# 04_16_2016_02.net
KiCad netlist of a schematic drawn in EAGLE
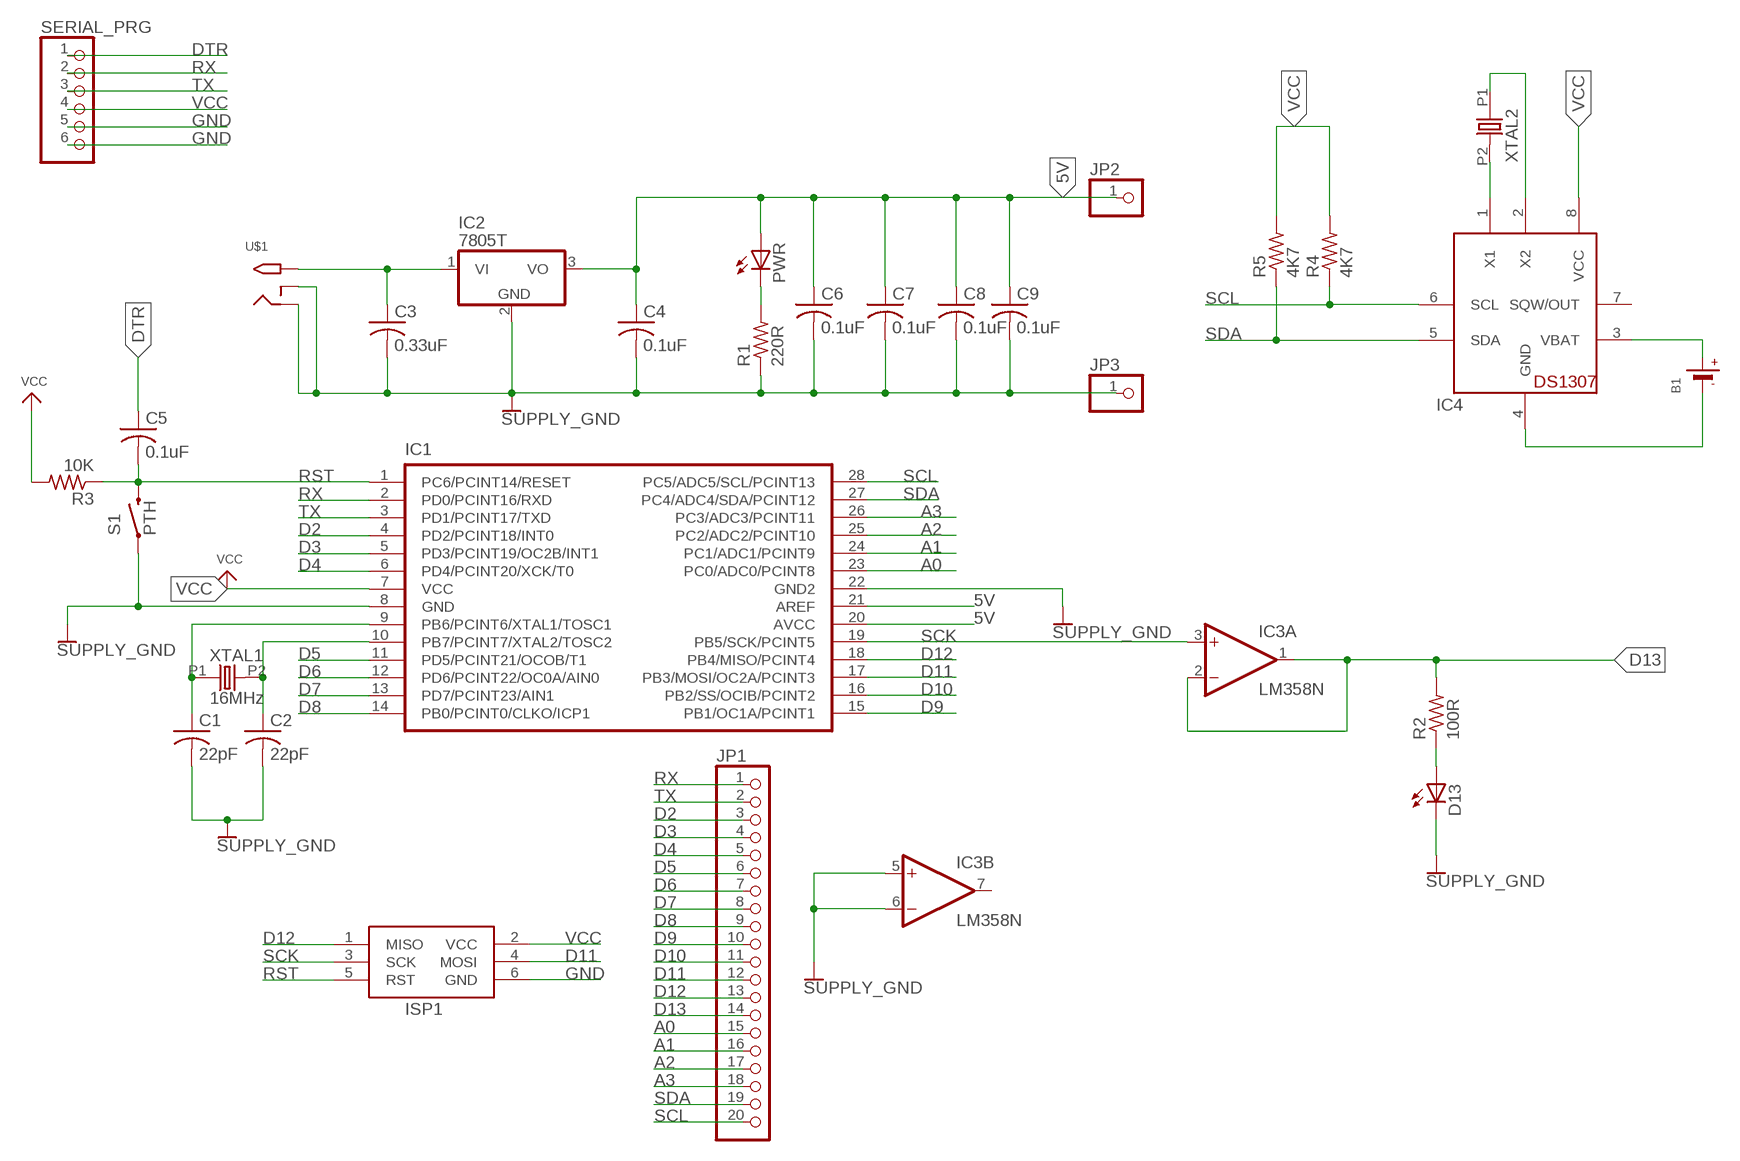
[diagram p0: schematic, sheet 1]

(export (version "E")
  (design (tool "Eeschema 10.0.6"))
  (components
    (comp (ref "B1")
      (value "BATTERYCR2032")
      (footprint "eagle-import:CR2032")
      (libsource (lib "eagle-import") (part "BATTERYCR2032"))
    )
    (comp (ref "C1")
      (value "22pF")
      (footprint "eagle-import:C050-025X075")
      (libsource (lib "eagle-import") (part "C-US050-025X075"))
    )
    (comp (ref "C2")
      (value "22pF")
      (footprint "eagle-import:C050-025X075")
      (libsource (lib "eagle-import") (part "C-US050-025X075"))
    )
    (comp (ref "C3")
      (value "0.33uF")
      (footprint "eagle-import:C050-025X075")
      (libsource (lib "eagle-import") (part "C-US050-025X075"))
    )
    (comp (ref "C4")
      (value "0.1uF")
      (footprint "eagle-import:C050-025X075")
      (libsource (lib "eagle-import") (part "C-US050-025X075"))
    )
    (comp (ref "C5")
      (value "0.1uF")
      (footprint "eagle-import:C050-025X075")
      (libsource (lib "eagle-import") (part "C-US050-025X075"))
    )
    (comp (ref "C6")
      (value "0.1uF")
      (footprint "eagle-import:C050-025X075")
      (libsource (lib "eagle-import") (part "C-US050-025X075"))
    )
    (comp (ref "C7")
      (value "0.1uF")
      (footprint "eagle-import:C050-025X075")
      (libsource (lib "eagle-import") (part "C-US050-025X075"))
    )
    (comp (ref "C8")
      (value "0.1uF")
      (footprint "eagle-import:C050-025X075")
      (libsource (lib "eagle-import") (part "C-US050-025X075"))
    )
    (comp (ref "C9")
      (value "0.1uF")
      (footprint "eagle-import:C050-025X075")
      (libsource (lib "eagle-import") (part "C-US050-025X075"))
    )
    (comp (ref "D13")
      (value "LED5MM")
      (footprint "eagle-import:LED5MM")
      (libsource (lib "eagle-import") (part "LED5MM"))
    )
    (comp (ref "IC1")
      (value "IC_UC_ATMEGA328PDIL")
      (footprint "eagle-import:DIL28-N")
      (libsource (lib "eagle-import") (part "IC_UC_ATMEGA328PDIL"))
    )
    (comp (ref "IC2")
      (value "7805T")
      (footprint "eagle-import:TO220H")
      (libsource (lib "eagle-import") (part "78T05"))
    )
    (comp (ref "IC3")
      (value "LM358N")
      (footprint "eagle-import:DIL08")
      (libsource (lib "eagle-import") (part "LM358N"))
    )
    (comp (ref "IC4")
      (value "DS1307")
      (footprint "eagle-import:DIL08")
      (libsource (lib "eagle-import") (part "DS1307"))
    )
    (comp (ref "ISP1")
      (value "AVRISP-6")
      (footprint "eagle-import:AVRISP")
      (libsource (lib "eagle-import") (part "AVRISP-6"))
    )
    (comp (ref "JP1")
      (value "PINHD-1X20-BIG")
      (footprint "eagle-import:1X20-BIG")
      (libsource (lib "eagle-import") (part "PINHD-1X20-BIG"))
    )
    (comp (ref "JP2")
      (value "PINHD-1X1")
      (footprint "eagle-import:1X01")
      (libsource (lib "eagle-import") (part "PINHD-1X1"))
    )
    (comp (ref "JP3")
      (value "PINHD-1X1")
      (footprint "eagle-import:1X01")
      (libsource (lib "eagle-import") (part "PINHD-1X1"))
    )
    (comp (ref "PWR")
      (value "LED5MM")
      (footprint "eagle-import:LED5MM")
      (libsource (lib "eagle-import") (part "LED5MM"))
    )
    (comp (ref "R1")
      (value "220R")
      (footprint "eagle-import:0207_10")
      (libsource (lib "eagle-import") (part "R-US_0207/10"))
    )
    (comp (ref "R2")
      (value "100R")
      (footprint "eagle-import:0207_10")
      (libsource (lib "eagle-import") (part "R-US_0207/10"))
    )
    (comp (ref "R3")
      (value "10K")
      (footprint "eagle-import:0207_10")
      (libsource (lib "eagle-import") (part "R-US_0207/10"))
    )
    (comp (ref "R4")
      (value "4K7")
      (footprint "eagle-import:0207_10")
      (libsource (lib "eagle-import") (part "R-US_0207/10"))
    )
    (comp (ref "R5")
      (value "4K7")
      (footprint "eagle-import:0207_10")
      (libsource (lib "eagle-import") (part "R-US_0207/10"))
    )
    (comp (ref "S1")
      (value "PTH")
      (footprint "eagle-import:TACTILE-PTH")
      (libsource (lib "eagle-import") (part "SWITCH-MOMENTARY-2PTH"))
    )
    (comp (ref "SERIAL_PRG")
      (value "PINHD-1X6")
      (footprint "eagle-import:1X06")
      (libsource (lib "eagle-import") (part "PINHD-1X6"))
    )
    (comp (ref "U$1")
      (value "2.1MMJACKTHM")
      (footprint "eagle-import:PJ-102A")
      (libsource (lib "eagle-import") (part "2.1MMJACKTHM"))
    )
    (comp (ref "XTAL1")
      (value "16MHz")
      (footprint "eagle-import:HC-49U-PTH")
      (libsource (lib "eagle-import") (part "OSC-XTAL-HC-49U-PTH"))
    )
    (comp (ref "XTAL2")
      (value "OSC-XTALTC-26")
      (footprint "eagle-import:TC-26")
      (libsource (lib "eagle-import") (part "OSC-XTALTC-26"))
    )
  )
  (nets
    (net (code "1") (name "/A0") (class "Default")
      (node (ref "IC1") (pin "23") (pinfunction "PC0/ADC0/PCINT8_23") (pintype "bidirectional"))
      (node (ref "JP1") (pin "15") (pinfunction "15_15") (pintype "passive"))
    )
    (net (code "2") (name "/A1") (class "Default")
      (node (ref "IC1") (pin "24") (pinfunction "PC1/ADC1/PCINT9_24") (pintype "bidirectional"))
      (node (ref "JP1") (pin "16") (pinfunction "16_16") (pintype "passive"))
    )
    (net (code "3") (name "/A2") (class "Default")
      (node (ref "IC1") (pin "25") (pinfunction "PC2/ADC2/PCINT10_25") (pintype "bidirectional"))
      (node (ref "JP1") (pin "17") (pinfunction "17_17") (pintype "passive"))
    )
    (net (code "4") (name "/A3") (class "Default")
      (node (ref "IC1") (pin "26") (pinfunction "PC3/ADC3/PCINT11_26") (pintype "bidirectional"))
      (node (ref "JP1") (pin "18") (pinfunction "18_18") (pintype "passive"))
    )
    (net (code "5") (name "/D2") (class "Default")
      (node (ref "IC1") (pin "4") (pinfunction "PD2/PCINT18/INT0_4") (pintype "bidirectional"))
      (node (ref "JP1") (pin "3") (pinfunction "3_3") (pintype "passive"))
    )
    (net (code "6") (name "/D3") (class "Default")
      (node (ref "IC1") (pin "5") (pinfunction "PD3/PCINT19/OC2B/INT1_5") (pintype "bidirectional"))
      (node (ref "JP1") (pin "4") (pinfunction "4_4") (pintype "passive"))
    )
    (net (code "7") (name "/D4") (class "Default")
      (node (ref "IC1") (pin "6") (pinfunction "PD4/PCINT20/XCK/T0_6") (pintype "bidirectional"))
      (node (ref "JP1") (pin "5") (pinfunction "5_5") (pintype "passive"))
    )
    (net (code "8") (name "/D5") (class "Default")
      (node (ref "IC1") (pin "11") (pinfunction "PD5/PCINT21/OCOB/T1_11") (pintype "bidirectional"))
      (node (ref "JP1") (pin "6") (pinfunction "6_6") (pintype "passive"))
    )
    (net (code "9") (name "/D6") (class "Default")
      (node (ref "IC1") (pin "12") (pinfunction "PD6/PCINT22/OC0A/AIN0_12") (pintype "bidirectional"))
      (node (ref "JP1") (pin "7") (pinfunction "7_7") (pintype "passive"))
    )
    (net (code "10") (name "/D7") (class "Default")
      (node (ref "IC1") (pin "13") (pinfunction "PD7/PCINT23/AIN1_13") (pintype "bidirectional"))
      (node (ref "JP1") (pin "8") (pinfunction "8_8") (pintype "passive"))
    )
    (net (code "11") (name "/D8") (class "Default")
      (node (ref "IC1") (pin "14") (pinfunction "PB0/PCINT0/CLKO/ICP1_14") (pintype "bidirectional"))
      (node (ref "JP1") (pin "9") (pinfunction "9_9") (pintype "passive"))
    )
    (net (code "12") (name "/D9") (class "Default")
      (node (ref "IC1") (pin "15") (pinfunction "PB1/OC1A/PCINT1_15") (pintype "bidirectional"))
      (node (ref "JP1") (pin "10") (pinfunction "10_10") (pintype "passive"))
    )
    (net (code "13") (name "/D10") (class "Default")
      (node (ref "IC1") (pin "16") (pinfunction "PB2/SS/OCIB/PCINT2_16") (pintype "bidirectional"))
      (node (ref "JP1") (pin "11") (pinfunction "11_11") (pintype "passive"))
    )
    (net (code "14") (name "/D11") (class "Default")
      (node (ref "IC1") (pin "17") (pinfunction "PB3/MOSI/OC2A/PCINT3_17") (pintype "bidirectional"))
      (node (ref "ISP1") (pin "4") (pinfunction "MOSI_4") (pintype "output"))
      (node (ref "JP1") (pin "12") (pinfunction "12_12") (pintype "passive"))
    )
    (net (code "15") (name "/D12") (class "Default")
      (node (ref "IC1") (pin "18") (pinfunction "PB4/MISO/PCINT4_18") (pintype "bidirectional"))
      (node (ref "ISP1") (pin "1") (pinfunction "MISO_1") (pintype "input"))
      (node (ref "JP1") (pin "13") (pinfunction "13_13") (pintype "passive"))
    )
    (net (code "16") (name "/RST") (class "Default")
      (node (ref "C5") (pin "2") (pinfunction "2_2") (pintype "passive"))
      (node (ref "IC1") (pin "1") (pinfunction "PC6/PCINT14/RESET_1") (pintype "bidirectional"))
      (node (ref "ISP1") (pin "5") (pinfunction "RST_5") (pintype "output"))
      (node (ref "R3") (pin "1") (pinfunction "1_1") (pintype "passive"))
      (node (ref "S1") (pin "3") (pinfunction "2_3") (pintype "passive"))
    )
    (net (code "17") (name "/RX") (class "Default")
      (node (ref "IC1") (pin "2") (pinfunction "PD0/PCINT16/RXD_2") (pintype "bidirectional"))
      (node (ref "JP1") (pin "1") (pinfunction "1_1") (pintype "passive"))
      (node (ref "SERIAL_PRG") (pin "2") (pinfunction "2_2") (pintype "passive"))
    )
    (net (code "18") (name "/SCK") (class "Default")
      (node (ref "IC1") (pin "19") (pinfunction "PB5/SCK/PCINT5_19") (pintype "bidirectional"))
      (node (ref "IC3") (pin "3") (pinfunction "+IN_3") (pintype "input"))
      (node (ref "ISP1") (pin "3") (pinfunction "SCK_3") (pintype "output"))
    )
    (net (code "19") (name "/SCL") (class "Default")
      (node (ref "IC1") (pin "28") (pinfunction "PC5/ADC5/SCL/PCINT13_28") (pintype "bidirectional"))
      (node (ref "IC4") (pin "6") (pinfunction "SCL_6") (pintype "bidirectional"))
      (node (ref "JP1") (pin "20") (pinfunction "20_20") (pintype "passive"))
      (node (ref "R4") (pin "1") (pinfunction "1_1") (pintype "passive"))
    )
    (net (code "20") (name "/SDA") (class "Default")
      (node (ref "IC1") (pin "27") (pinfunction "PC4/ADC4/SDA/PCINT12_27") (pintype "bidirectional"))
      (node (ref "IC4") (pin "5") (pinfunction "SDA_5") (pintype "bidirectional"))
      (node (ref "JP1") (pin "19") (pinfunction "19_19") (pintype "passive"))
      (node (ref "R5") (pin "1") (pinfunction "1_1") (pintype "passive"))
    )
    (net (code "21") (name "/TX") (class "Default")
      (node (ref "IC1") (pin "3") (pinfunction "PD1/PCINT17/TXD_3") (pintype "bidirectional"))
      (node (ref "JP1") (pin "2") (pinfunction "2_2") (pintype "passive"))
      (node (ref "SERIAL_PRG") (pin "3") (pinfunction "3_3") (pintype "passive"))
    )
    (net (code "22") (name "5V") (class "Default")
      (node (ref "C4") (pin "1") (pinfunction "1_1") (pintype "passive"))
      (node (ref "C6") (pin "1") (pinfunction "1_1") (pintype "passive"))
      (node (ref "C7") (pin "1") (pinfunction "1_1") (pintype "passive"))
      (node (ref "C8") (pin "1") (pinfunction "1_1") (pintype "passive"))
      (node (ref "C9") (pin "1") (pinfunction "1_1") (pintype "passive"))
      (node (ref "IC1") (pin "20") (pinfunction "AVCC_20") (pintype "bidirectional"))
      (node (ref "IC1") (pin "21") (pinfunction "AREF_21") (pintype "bidirectional"))
      (node (ref "IC2") (pin "3") (pinfunction "VO_3") (pintype "passive"))
      (node (ref "JP2") (pin "1") (pinfunction "1_1") (pintype "passive"))
      (node (ref "PWR") (pin "A") (pinfunction "A_A") (pintype "passive"))
    )
    (net (code "23") (name "D13") (class "Default")
      (node (ref "IC3") (pin "1") (pinfunction "OUT_1") (pintype "output"))
      (node (ref "IC3") (pin "2") (pinfunction "-IN_2") (pintype "input"))
      (node (ref "JP1") (pin "14") (pinfunction "14_14") (pintype "passive"))
      (node (ref "R2") (pin "2") (pinfunction "2_2") (pintype "passive"))
    )
    (net (code "24") (name "DTR") (class "Default")
      (node (ref "C5") (pin "1") (pinfunction "1_1") (pintype "passive"))
      (node (ref "SERIAL_PRG") (pin "1") (pinfunction "1_1") (pintype "passive"))
    )
    (net (code "25") (name "Net-(D13-PadA)") (class "Default")
      (node (ref "D13") (pin "A") (pinfunction "A_A") (pintype "passive"))
      (node (ref "R2") (pin "1") (pinfunction "1_1") (pintype "passive"))
    )
    (net (code "26") (name "Net-(IC1-PB6{slash}PCINT6{slash}XTAL1{slash}TOSC1)") (class "Default")
      (node (ref "C1") (pin "1") (pinfunction "1_1") (pintype "passive"))
      (node (ref "IC1") (pin "9") (pinfunction "PB6/PCINT6/XTAL1/TOSC1_9") (pintype "bidirectional"))
      (node (ref "XTAL1") (pin "P1") (pinfunction "1_P1") (pintype "passive"))
    )
    (net (code "27") (name "Net-(IC1-PB7{slash}PCINT7{slash}XTAL2{slash}TOSC2)") (class "Default")
      (node (ref "C2") (pin "1") (pinfunction "1_1") (pintype "passive"))
      (node (ref "IC1") (pin "10") (pinfunction "PB7/PCINT7/XTAL2/TOSC2_10") (pintype "bidirectional"))
      (node (ref "XTAL1") (pin "P2") (pinfunction "2_P2") (pintype "passive"))
    )
    (net (code "28") (name "Net-(IC2-VI)") (class "Default")
      (node (ref "C3") (pin "1") (pinfunction "1_1") (pintype "passive"))
      (node (ref "IC2") (pin "1") (pinfunction "VI_1") (pintype "input"))
      (node (ref "U$1") (pin "TIP") (pinfunction "TIP_TIP") (pintype "bidirectional"))
    )
    (net (code "29") (name "Net-(IC4-GND)") (class "Default")
      (node (ref "B1") (pin "-") (pinfunction "-_-") (pintype "passive"))
      (node (ref "IC4") (pin "4") (pinfunction "GND_4") (pintype "power_in"))
    )
    (net (code "30") (name "Net-(IC4-VBAT)") (class "Default")
      (node (ref "B1") (pin "+") (pinfunction "+_+") (pintype "passive"))
      (node (ref "IC4") (pin "3") (pinfunction "VBAT_3") (pintype "power_in"))
    )
    (net (code "31") (name "Net-(IC4-X1)") (class "Default")
      (node (ref "IC4") (pin "1") (pinfunction "X1_1") (pintype "passive"))
      (node (ref "XTAL2") (pin "P2") (pinfunction "2_P2") (pintype "passive"))
    )
    (net (code "32") (name "Net-(IC4-X2)") (class "Default")
      (node (ref "IC4") (pin "2") (pinfunction "X2_2") (pintype "passive"))
      (node (ref "XTAL2") (pin "P1") (pinfunction "1_P1") (pintype "passive"))
    )
    (net (code "33") (name "Net-(PWR-C)") (class "Default")
      (node (ref "PWR") (pin "K") (pinfunction "C_K") (pintype "passive"))
      (node (ref "R1") (pin "2") (pinfunction "2_2") (pintype "passive"))
    )
    (net (code "34") (name "SUPPLY_GND") (class "Default")
      (node (ref "C1") (pin "2") (pinfunction "2_2") (pintype "passive"))
      (node (ref "C2") (pin "2") (pinfunction "2_2") (pintype "passive"))
      (node (ref "C3") (pin "2") (pinfunction "2_2") (pintype "passive"))
      (node (ref "C4") (pin "2") (pinfunction "2_2") (pintype "passive"))
      (node (ref "C6") (pin "2") (pinfunction "2_2") (pintype "passive"))
      (node (ref "C7") (pin "2") (pinfunction "2_2") (pintype "passive"))
      (node (ref "C8") (pin "2") (pinfunction "2_2") (pintype "passive"))
      (node (ref "C9") (pin "2") (pinfunction "2_2") (pintype "passive"))
      (node (ref "D13") (pin "K") (pinfunction "C_K") (pintype "passive"))
      (node (ref "IC1") (pin "22") (pinfunction "GND2_22") (pintype "bidirectional"))
      (node (ref "IC1") (pin "8") (pinfunction "GND_8") (pintype "bidirectional"))
      (node (ref "IC2") (pin "2") (pinfunction "GND_2") (pintype "passive"))
      (node (ref "IC3") (pin "5") (pinfunction "+IN_5") (pintype "input"))
      (node (ref "IC3") (pin "6") (pinfunction "-IN_6") (pintype "input"))
      (node (ref "ISP1") (pin "6") (pinfunction "GND_6") (pintype "power_in"))
      (node (ref "JP3") (pin "1") (pinfunction "1_1") (pintype "passive"))
      (node (ref "R1") (pin "1") (pinfunction "1_1") (pintype "passive"))
      (node (ref "S1") (pin "1") (pinfunction "1_1") (pintype "passive"))
      (node (ref "SERIAL_PRG") (pin "5") (pinfunction "5_5") (pintype "passive"))
      (node (ref "SERIAL_PRG") (pin "6") (pinfunction "6_6") (pintype "passive"))
      (node (ref "U$1") (pin "RING") (pinfunction "RING_RING") (pintype "bidirectional"))
      (node (ref "U$1") (pin "RING_SW") (pinfunction "RING_SW_RING_SW") (pintype "bidirectional"))
    )
    (net (code "35") (name "VCC") (class "Default")
      (node (ref "IC1") (pin "7") (pinfunction "VCC_7") (pintype "bidirectional"))
      (node (ref "IC4") (pin "8") (pinfunction "VCC_8") (pintype "power_in"))
      (node (ref "ISP1") (pin "2") (pinfunction "VCC_2") (pintype "power_in"))
      (node (ref "R3") (pin "2") (pinfunction "2_2") (pintype "passive"))
      (node (ref "R4") (pin "2") (pinfunction "2_2") (pintype "passive"))
      (node (ref "R5") (pin "2") (pinfunction "2_2") (pintype "passive"))
      (node (ref "SERIAL_PRG") (pin "4") (pinfunction "4_4") (pintype "passive"))
    )
    (net (code "36") (name "unconnected-(IC3B-OUT-Pad7)") (class "Default")
      (node (ref "IC3") (pin "7") (pinfunction "OUT_7") (pintype "output"))
    )
    (net (code "37") (name "unconnected-(IC4-SQW{slash}OUT-Pad7)") (class "Default")
      (node (ref "IC4") (pin "7") (pinfunction "SQW/OUT_7") (pintype "bidirectional"))
    )
  )
)
